# rev1.net
KiCad netlist of a schematic drawn in EAGLE
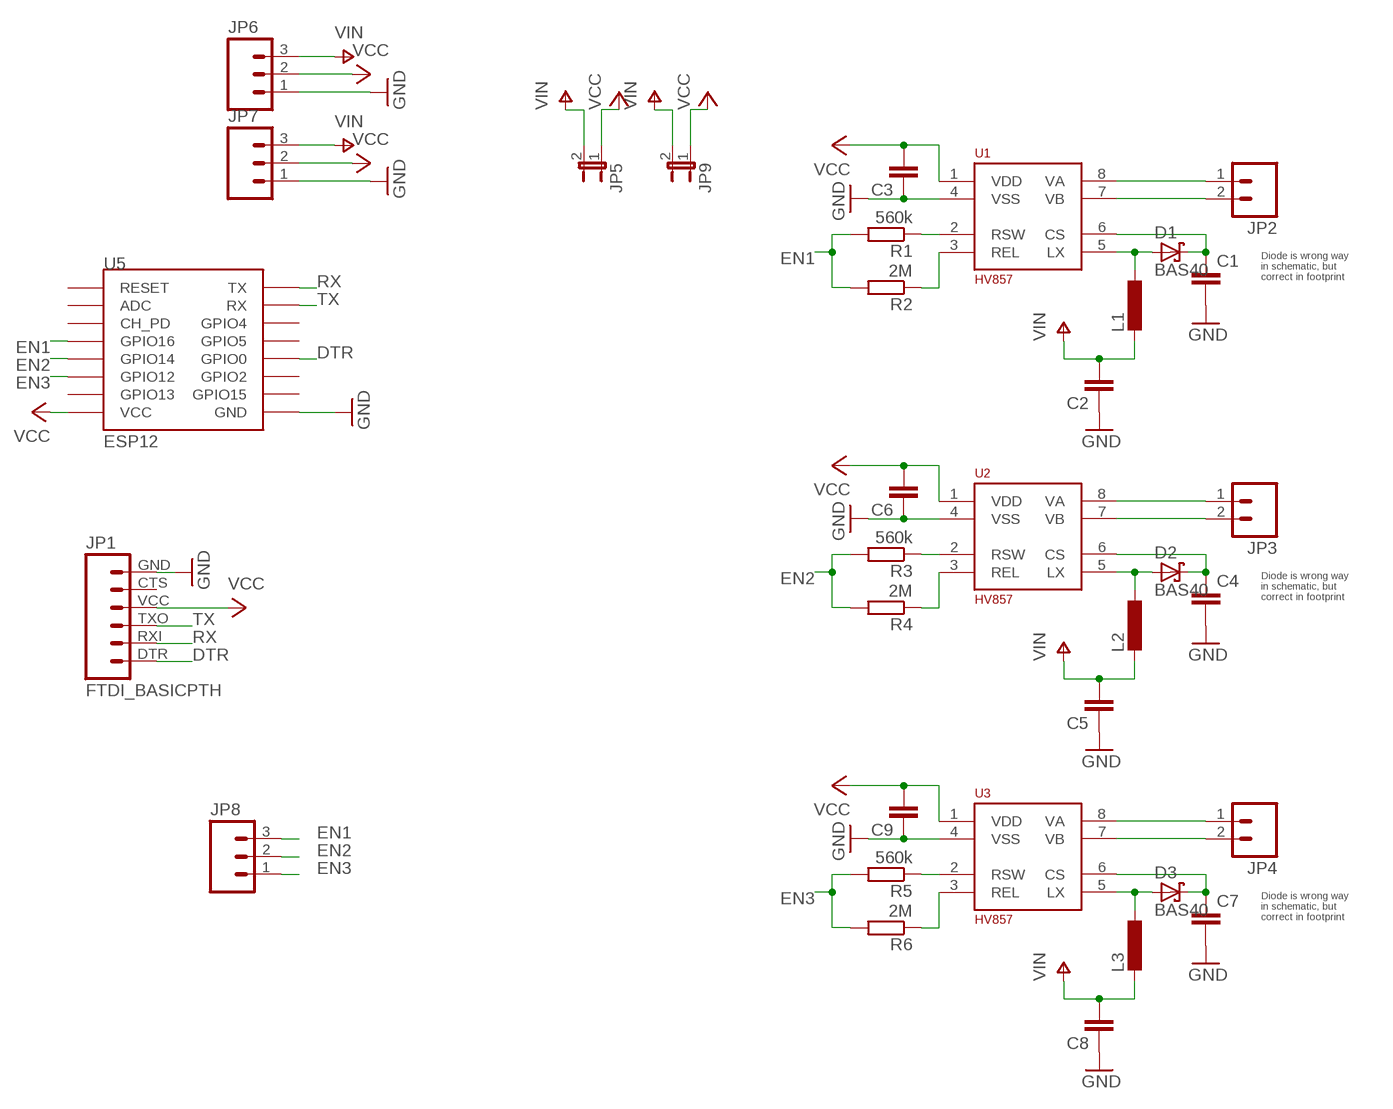
[diagram p0: schematic, sheet 1]

(export (version "E")
  (design (tool "Eeschema 10.0.6"))
  (components
    (comp (ref "C1")
      (value "C-EUC0603")
      (footprint "eagle-import:C0603")
      (libsource (lib "eagle-import") (part "C-EUC0603"))
    )
    (comp (ref "C2")
      (value "C-EUC0603")
      (footprint "eagle-import:C0603")
      (libsource (lib "eagle-import") (part "C-EUC0603"))
    )
    (comp (ref "C3")
      (value "C-EUC0603")
      (footprint "eagle-import:C0603")
      (libsource (lib "eagle-import") (part "C-EUC0603"))
    )
    (comp (ref "C4")
      (value "C-EUC0603")
      (footprint "eagle-import:C0603")
      (libsource (lib "eagle-import") (part "C-EUC0603"))
    )
    (comp (ref "C5")
      (value "C-EUC0603")
      (footprint "eagle-import:C0603")
      (libsource (lib "eagle-import") (part "C-EUC0603"))
    )
    (comp (ref "C6")
      (value "C-EUC0603")
      (footprint "eagle-import:C0603")
      (libsource (lib "eagle-import") (part "C-EUC0603"))
    )
    (comp (ref "C7")
      (value "C-EUC0603")
      (footprint "eagle-import:C0603")
      (libsource (lib "eagle-import") (part "C-EUC0603"))
    )
    (comp (ref "C8")
      (value "C-EUC0603")
      (footprint "eagle-import:C0603")
      (libsource (lib "eagle-import") (part "C-EUC0603"))
    )
    (comp (ref "C9")
      (value "C-EUC0603")
      (footprint "eagle-import:C0603")
      (libsource (lib "eagle-import") (part "C-EUC0603"))
    )
    (comp (ref "D1")
      (value "BAS40")
      (footprint "eagle-import:SOT23")
      (libsource (lib "eagle-import") (part "BAS40"))
    )
    (comp (ref "D2")
      (value "BAS40")
      (footprint "eagle-import:SOT23")
      (libsource (lib "eagle-import") (part "BAS40"))
    )
    (comp (ref "D3")
      (value "BAS40")
      (footprint "eagle-import:SOT23")
      (libsource (lib "eagle-import") (part "BAS40"))
    )
    (comp (ref "JP1")
      (value "FTDI_BASICPTH")
      (footprint "eagle-import:FTDI_BASIC")
      (libsource (lib "eagle-import") (part "FTDI_BASICPTH"))
    )
    (comp (ref "JP2")
      (value "M02PTH")
      (footprint "eagle-import:1X02")
      (libsource (lib "eagle-import") (part "M02PTH"))
    )
    (comp (ref "JP3")
      (value "M02PTH")
      (footprint "eagle-import:1X02")
      (libsource (lib "eagle-import") (part "M02PTH"))
    )
    (comp (ref "JP4")
      (value "M02PTH")
      (footprint "eagle-import:1X02")
      (libsource (lib "eagle-import") (part "M02PTH"))
    )
    (comp (ref "JP5")
      (value "JUMPER-2SMD-NC")
      (footprint "eagle-import:SJ_2S")
      (libsource (lib "eagle-import") (part "JUMPER-2SMD-NC"))
    )
    (comp (ref "JP6")
      (value "M03PTH")
      (footprint "eagle-import:1X03")
      (libsource (lib "eagle-import") (part "M03PTH"))
    )
    (comp (ref "JP7")
      (value "M03PTH")
      (footprint "eagle-import:1X03")
      (libsource (lib "eagle-import") (part "M03PTH"))
    )
    (comp (ref "JP8")
      (value "M03PTH")
      (footprint "eagle-import:1X03")
      (libsource (lib "eagle-import") (part "M03PTH"))
    )
    (comp (ref "JP9")
      (value "JUMPER-2SMD-NC")
      (footprint "eagle-import:SJ_2S")
      (libsource (lib "eagle-import") (part "JUMPER-2SMD-NC"))
    )
    (comp (ref "L1")
      (value "L-EUL3225M")
      (footprint "eagle-import:L3225M")
      (libsource (lib "eagle-import") (part "L-EUL3225M"))
    )
    (comp (ref "L2")
      (value "L-EUL3225M")
      (footprint "eagle-import:L3225M")
      (libsource (lib "eagle-import") (part "L-EUL3225M"))
    )
    (comp (ref "L3")
      (value "L-EUL3225M")
      (footprint "eagle-import:L3225M")
      (libsource (lib "eagle-import") (part "L-EUL3225M"))
    )
    (comp (ref "R1")
      (value "560k")
      (footprint "eagle-import:R0603")
      (libsource (lib "eagle-import") (part "R-EU_R0603"))
    )
    (comp (ref "R2")
      (value "2M")
      (footprint "eagle-import:R0603")
      (libsource (lib "eagle-import") (part "R-EU_R0603"))
    )
    (comp (ref "R3")
      (value "560k")
      (footprint "eagle-import:R0603")
      (libsource (lib "eagle-import") (part "R-EU_R0603"))
    )
    (comp (ref "R4")
      (value "2M")
      (footprint "eagle-import:R0603")
      (libsource (lib "eagle-import") (part "R-EU_R0603"))
    )
    (comp (ref "R5")
      (value "560k")
      (footprint "eagle-import:R0603")
      (libsource (lib "eagle-import") (part "R-EU_R0603"))
    )
    (comp (ref "R6")
      (value "2M")
      (footprint "eagle-import:R0603")
      (libsource (lib "eagle-import") (part "R-EU_R0603"))
    )
    (comp (ref "U1")
      (value "HV857")
      (footprint "eagle-import:MSOP8")
      (libsource (lib "eagle-import") (part "HV857"))
    )
    (comp (ref "U2")
      (value "HV857")
      (footprint "eagle-import:MSOP8")
      (libsource (lib "eagle-import") (part "HV857"))
    )
    (comp (ref "U3")
      (value "HV857")
      (footprint "eagle-import:MSOP8")
      (libsource (lib "eagle-import") (part "HV857"))
    )
    (comp (ref "U5")
      (value "ESP12")
      (footprint "eagle-import:ESP12")
      (libsource (lib "eagle-import") (part "ESP12"))
    )
  )
  (nets
    (net (code "1") (name "/DTR") (class "Default")
      (node (ref "JP1") (pin "DTR") (pinfunction "1_DTR") (pintype "passive"))
      (node (ref "U5") (pin "GPIO0") (pinfunction "GPIO0_GPIO0") (pintype "bidirectional"))
    )
    (net (code "2") (name "/EN1") (class "Default")
      (node (ref "JP8") (pin "3") (pinfunction "3_3") (pintype "passive"))
      (node (ref "R1") (pin "2") (pinfunction "2_2") (pintype "passive"))
      (node (ref "R2") (pin "2") (pinfunction "2_2") (pintype "passive"))
      (node (ref "U5") (pin "GPIO16") (pinfunction "GPIO16_GPIO16") (pintype "bidirectional"))
    )
    (net (code "3") (name "/EN2") (class "Default")
      (node (ref "JP8") (pin "2") (pinfunction "2_2") (pintype "passive"))
      (node (ref "R3") (pin "2") (pinfunction "2_2") (pintype "passive"))
      (node (ref "R4") (pin "2") (pinfunction "2_2") (pintype "passive"))
      (node (ref "U5") (pin "GPIO14") (pinfunction "GPIO14_GPIO14") (pintype "bidirectional"))
    )
    (net (code "4") (name "/EN3") (class "Default")
      (node (ref "JP8") (pin "1") (pinfunction "1_1") (pintype "passive"))
      (node (ref "R5") (pin "2") (pinfunction "2_2") (pintype "passive"))
      (node (ref "R6") (pin "2") (pinfunction "2_2") (pintype "passive"))
      (node (ref "U5") (pin "GPIO12") (pinfunction "GPIO12_GPIO12") (pintype "bidirectional"))
    )
    (net (code "5") (name "/RX") (class "Default")
      (node (ref "JP1") (pin "RXI") (pinfunction "2_RXI") (pintype "passive"))
      (node (ref "U5") (pin "TX") (pinfunction "TX_TX") (pintype "bidirectional"))
    )
    (net (code "6") (name "/TX") (class "Default")
      (node (ref "JP1") (pin "TXO") (pinfunction "3_TXO") (pintype "passive"))
      (node (ref "U5") (pin "RX") (pinfunction "RX_RX") (pintype "bidirectional"))
    )
    (net (code "7") (name "GND") (class "Default")
      (node (ref "C1") (pin "2") (pinfunction "2_2") (pintype "passive"))
      (node (ref "C2") (pin "1") (pinfunction "1_1") (pintype "passive"))
      (node (ref "C3") (pin "1") (pinfunction "1_1") (pintype "passive"))
      (node (ref "C4") (pin "2") (pinfunction "2_2") (pintype "passive"))
      (node (ref "C5") (pin "1") (pinfunction "1_1") (pintype "passive"))
      (node (ref "C6") (pin "1") (pinfunction "1_1") (pintype "passive"))
      (node (ref "C7") (pin "2") (pinfunction "2_2") (pintype "passive"))
      (node (ref "C8") (pin "1") (pinfunction "1_1") (pintype "passive"))
      (node (ref "C9") (pin "1") (pinfunction "1_1") (pintype "passive"))
      (node (ref "JP1") (pin "GND") (pinfunction "6_GND") (pintype "passive"))
      (node (ref "JP6") (pin "1") (pinfunction "1_1") (pintype "passive"))
      (node (ref "JP7") (pin "1") (pinfunction "1_1") (pintype "passive"))
      (node (ref "U1") (pin "4") (pinfunction "VSS_4") (pintype "bidirectional"))
      (node (ref "U2") (pin "4") (pinfunction "VSS_4") (pintype "bidirectional"))
      (node (ref "U3") (pin "4") (pinfunction "VSS_4") (pintype "bidirectional"))
      (node (ref "U5") (pin "GND") (pinfunction "GND_GND") (pintype "bidirectional"))
    )
    (net (code "8") (name "Net-(D1-A)") (class "Default")
      (node (ref "D1") (pin "1") (pinfunction "A_1") (pintype "passive"))
      (node (ref "L1") (pin "1") (pinfunction "1_1") (pintype "passive"))
      (node (ref "U1") (pin "5") (pinfunction "LX_5") (pintype "bidirectional"))
    )
    (net (code "9") (name "Net-(D1-C)") (class "Default")
      (node (ref "C1") (pin "1") (pinfunction "1_1") (pintype "passive"))
      (node (ref "D1") (pin "3") (pinfunction "C_3") (pintype "passive"))
      (node (ref "U1") (pin "6") (pinfunction "CS_6") (pintype "bidirectional"))
    )
    (net (code "10") (name "Net-(D2-A)") (class "Default")
      (node (ref "D2") (pin "1") (pinfunction "A_1") (pintype "passive"))
      (node (ref "L2") (pin "1") (pinfunction "1_1") (pintype "passive"))
      (node (ref "U2") (pin "5") (pinfunction "LX_5") (pintype "bidirectional"))
    )
    (net (code "11") (name "Net-(D2-C)") (class "Default")
      (node (ref "C4") (pin "1") (pinfunction "1_1") (pintype "passive"))
      (node (ref "D2") (pin "3") (pinfunction "C_3") (pintype "passive"))
      (node (ref "U2") (pin "6") (pinfunction "CS_6") (pintype "bidirectional"))
    )
    (net (code "12") (name "Net-(D3-A)") (class "Default")
      (node (ref "D3") (pin "1") (pinfunction "A_1") (pintype "passive"))
      (node (ref "L3") (pin "1") (pinfunction "1_1") (pintype "passive"))
      (node (ref "U3") (pin "5") (pinfunction "LX_5") (pintype "bidirectional"))
    )
    (net (code "13") (name "Net-(D3-C)") (class "Default")
      (node (ref "C7") (pin "1") (pinfunction "1_1") (pintype "passive"))
      (node (ref "D3") (pin "3") (pinfunction "C_3") (pintype "passive"))
      (node (ref "U3") (pin "6") (pinfunction "CS_6") (pintype "bidirectional"))
    )
    (net (code "14") (name "Net-(U1-REL)") (class "Default")
      (node (ref "R2") (pin "1") (pinfunction "1_1") (pintype "passive"))
      (node (ref "U1") (pin "3") (pinfunction "REL_3") (pintype "bidirectional"))
    )
    (net (code "15") (name "Net-(U1-RSW)") (class "Default")
      (node (ref "R1") (pin "1") (pinfunction "1_1") (pintype "passive"))
      (node (ref "U1") (pin "2") (pinfunction "RSW_2") (pintype "bidirectional"))
    )
    (net (code "16") (name "Net-(U1-VA)") (class "Default")
      (node (ref "JP2") (pin "1") (pinfunction "1_1") (pintype "passive"))
      (node (ref "U1") (pin "8") (pinfunction "VA_8") (pintype "bidirectional"))
    )
    (net (code "17") (name "Net-(U1-VB)") (class "Default")
      (node (ref "JP2") (pin "2") (pinfunction "2_2") (pintype "passive"))
      (node (ref "U1") (pin "7") (pinfunction "VB_7") (pintype "bidirectional"))
    )
    (net (code "18") (name "Net-(U2-REL)") (class "Default")
      (node (ref "R4") (pin "1") (pinfunction "1_1") (pintype "passive"))
      (node (ref "U2") (pin "3") (pinfunction "REL_3") (pintype "bidirectional"))
    )
    (net (code "19") (name "Net-(U2-RSW)") (class "Default")
      (node (ref "R3") (pin "1") (pinfunction "1_1") (pintype "passive"))
      (node (ref "U2") (pin "2") (pinfunction "RSW_2") (pintype "bidirectional"))
    )
    (net (code "20") (name "Net-(U2-VA)") (class "Default")
      (node (ref "JP3") (pin "1") (pinfunction "1_1") (pintype "passive"))
      (node (ref "U2") (pin "8") (pinfunction "VA_8") (pintype "bidirectional"))
    )
    (net (code "21") (name "Net-(U2-VB)") (class "Default")
      (node (ref "JP3") (pin "2") (pinfunction "2_2") (pintype "passive"))
      (node (ref "U2") (pin "7") (pinfunction "VB_7") (pintype "bidirectional"))
    )
    (net (code "22") (name "Net-(U3-REL)") (class "Default")
      (node (ref "R6") (pin "1") (pinfunction "1_1") (pintype "passive"))
      (node (ref "U3") (pin "3") (pinfunction "REL_3") (pintype "bidirectional"))
    )
    (net (code "23") (name "Net-(U3-RSW)") (class "Default")
      (node (ref "R5") (pin "1") (pinfunction "1_1") (pintype "passive"))
      (node (ref "U3") (pin "2") (pinfunction "RSW_2") (pintype "bidirectional"))
    )
    (net (code "24") (name "Net-(U3-VA)") (class "Default")
      (node (ref "JP4") (pin "1") (pinfunction "1_1") (pintype "passive"))
      (node (ref "U3") (pin "8") (pinfunction "VA_8") (pintype "bidirectional"))
    )
    (net (code "25") (name "Net-(U3-VB)") (class "Default")
      (node (ref "JP4") (pin "2") (pinfunction "2_2") (pintype "passive"))
      (node (ref "U3") (pin "7") (pinfunction "VB_7") (pintype "bidirectional"))
    )
    (net (code "26") (name "VCC") (class "Default")
      (node (ref "C3") (pin "2") (pinfunction "2_2") (pintype "passive"))
      (node (ref "C6") (pin "2") (pinfunction "2_2") (pintype "passive"))
      (node (ref "C9") (pin "2") (pinfunction "2_2") (pintype "passive"))
      (node (ref "JP1") (pin "VCC") (pinfunction "4_VCC") (pintype "passive"))
      (node (ref "JP5") (pin "1") (pinfunction "1_1") (pintype "passive"))
      (node (ref "JP6") (pin "2") (pinfunction "2_2") (pintype "passive"))
      (node (ref "JP7") (pin "2") (pinfunction "2_2") (pintype "passive"))
      (node (ref "JP9") (pin "1") (pinfunction "1_1") (pintype "passive"))
      (node (ref "U1") (pin "1") (pinfunction "VDD_1") (pintype "bidirectional"))
      (node (ref "U2") (pin "1") (pinfunction "VDD_1") (pintype "bidirectional"))
      (node (ref "U3") (pin "1") (pinfunction "VDD_1") (pintype "bidirectional"))
      (node (ref "U5") (pin "VCC") (pinfunction "VCC_VCC") (pintype "bidirectional"))
    )
    (net (code "27") (name "VIN") (class "Default")
      (node (ref "C2") (pin "2") (pinfunction "2_2") (pintype "passive"))
      (node (ref "C5") (pin "2") (pinfunction "2_2") (pintype "passive"))
      (node (ref "C8") (pin "2") (pinfunction "2_2") (pintype "passive"))
      (node (ref "JP5") (pin "2") (pinfunction "2_2") (pintype "passive"))
      (node (ref "JP6") (pin "3") (pinfunction "3_3") (pintype "passive"))
      (node (ref "JP7") (pin "3") (pinfunction "3_3") (pintype "passive"))
      (node (ref "JP9") (pin "2") (pinfunction "2_2") (pintype "passive"))
      (node (ref "L1") (pin "2") (pinfunction "2_2") (pintype "passive"))
      (node (ref "L2") (pin "2") (pinfunction "2_2") (pintype "passive"))
      (node (ref "L3") (pin "2") (pinfunction "2_2") (pintype "passive"))
    )
    (net (code "28") (name "unconnected-(JP1-5-PadCTS)") (class "Default")
      (node (ref "JP1") (pin "CTS") (pinfunction "5_CTS") (pintype "passive"))
    )
    (net (code "29") (name "unconnected-(U5-PadADC)") (class "Default")
      (node (ref "U5") (pin "ADC") (pinfunction "ADC_ADC") (pintype "bidirectional"))
    )
    (net (code "30") (name "unconnected-(U5-PadCH_PD)") (class "Default")
      (node (ref "U5") (pin "CH_PD") (pinfunction "CH_PD_CH_PD") (pintype "bidirectional"))
    )
    (net (code "31") (name "unconnected-(U5-PadGPIO2)") (class "Default")
      (node (ref "U5") (pin "GPIO2") (pinfunction "GPIO2_GPIO2") (pintype "bidirectional"))
    )
    (net (code "32") (name "unconnected-(U5-PadGPIO4)") (class "Default")
      (node (ref "U5") (pin "GPIO4") (pinfunction "GPIO4_GPIO4") (pintype "bidirectional"))
    )
    (net (code "33") (name "unconnected-(U5-PadGPIO5)") (class "Default")
      (node (ref "U5") (pin "GPIO5") (pinfunction "GPIO5_GPIO5") (pintype "bidirectional"))
    )
    (net (code "34") (name "unconnected-(U5-PadGPIO13)") (class "Default")
      (node (ref "U5") (pin "GPIO13") (pinfunction "GPIO13_GPIO13") (pintype "bidirectional"))
    )
    (net (code "35") (name "unconnected-(U5-PadGPIO15)") (class "Default")
      (node (ref "U5") (pin "GPIO15") (pinfunction "GPIO15_GPIO15") (pintype "bidirectional"))
    )
    (net (code "36") (name "unconnected-(U5-PadRESET)") (class "Default")
      (node (ref "U5") (pin "RESET") (pinfunction "RESET_RESET") (pintype "bidirectional"))
    )
  )
)
